# 2505_IDS_DL_BAT.net
KiCad netlist of a schematic drawn in Altium Designer
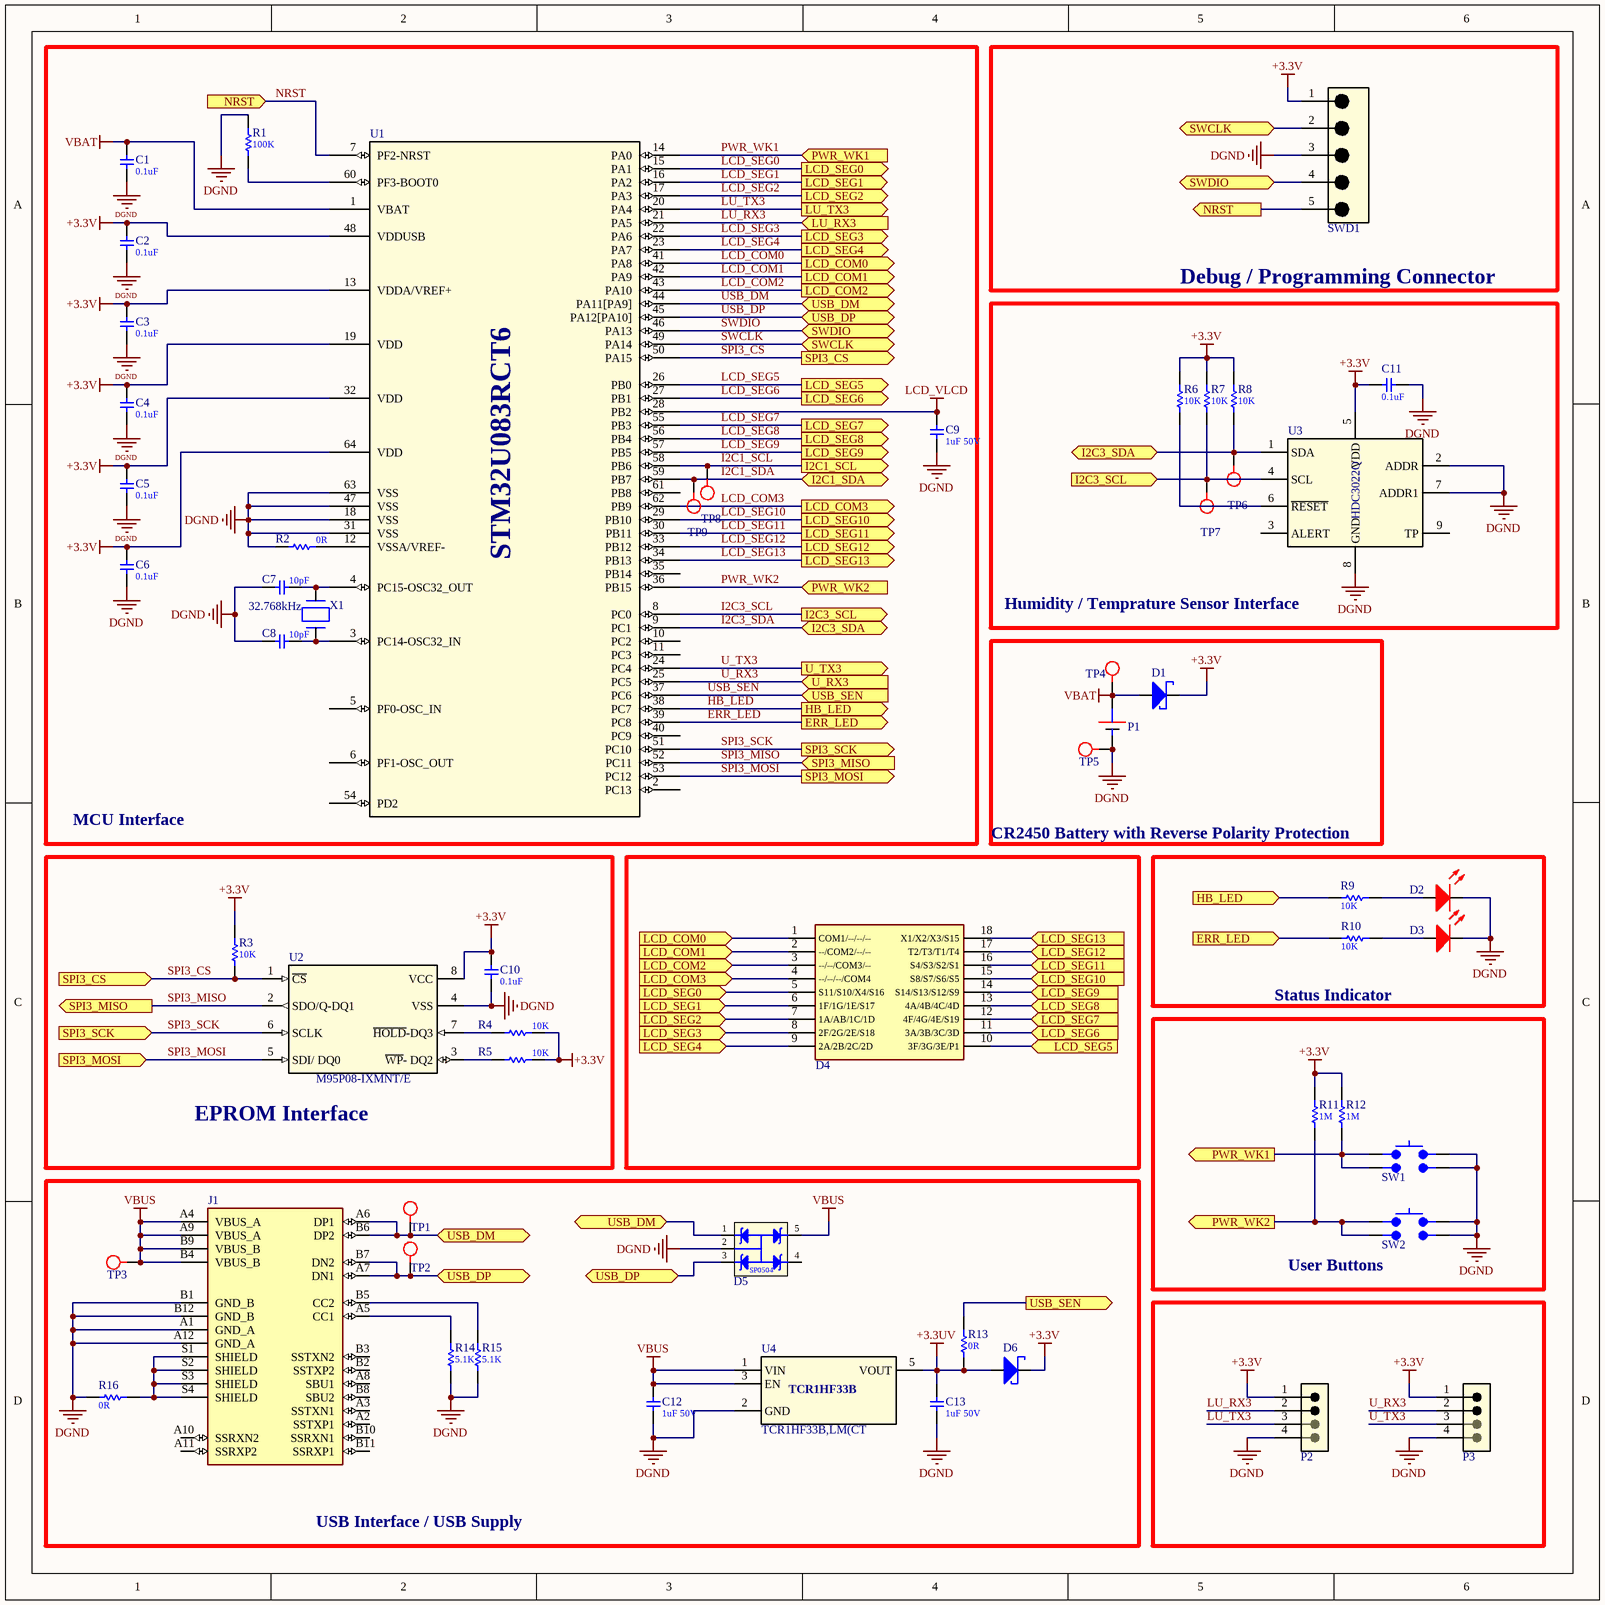
[diagram p0: 2505_IDS_DL_BAT.SchDoc]

(export (version "E")
  (design (tool "Eeschema 10.0.6"))
  (components
    (comp (ref "C1")
      (value "0.1uF")
      (footprint "C_0603 (1608 Metric)")
      (fields
        (field (name "MANUFACTURER PART NO") "CL10B104KB8NNWC")
        (field (name "Comment") "CAP CER 0.1UF 50V X7R 0603")
      )
      (libsource (lib "Capacitor") (part "CAP CER 0.1UF 50V X7R 0603"))
    )
    (comp (ref "C2")
      (value "0.1uF")
      (footprint "C_0603 (1608 Metric)")
      (fields
        (field (name "MANUFACTURER PART NO") "CL10B104KB8NNWC")
        (field (name "Comment") "CAP CER 0.1UF 50V X7R 0603")
      )
      (libsource (lib "Capacitor") (part "CAP CER 0.1UF 50V X7R 0603"))
    )
    (comp (ref "C3")
      (value "0.1uF")
      (footprint "C_0603 (1608 Metric)")
      (fields
        (field (name "MANUFACTURER PART NO") "CL10B104KB8NNWC")
        (field (name "Comment") "CAP CER 0.1UF 50V X7R 0603")
      )
      (libsource (lib "Capacitor") (part "CAP CER 0.1UF 50V X7R 0603"))
    )
    (comp (ref "C4")
      (value "0.1uF")
      (footprint "C_0603 (1608 Metric)")
      (fields
        (field (name "MANUFACTURER PART NO") "CL10B104KB8NNWC")
        (field (name "Comment") "CAP CER 0.1UF 50V X7R 0603")
      )
      (libsource (lib "Capacitor") (part "CAP CER 0.1UF 50V X7R 0603"))
    )
    (comp (ref "C5")
      (value "0.1uF")
      (footprint "C_0603 (1608 Metric)")
      (fields
        (field (name "MANUFACTURER PART NO") "CL10B104KB8NNWC")
        (field (name "Comment") "CAP CER 0.1UF 50V X7R 0603")
      )
      (libsource (lib "Capacitor") (part "CAP CER 0.1UF 50V X7R 0603"))
    )
    (comp (ref "C6")
      (value "0.1uF")
      (footprint "C_0603 (1608 Metric)")
      (fields
        (field (name "MANUFACTURER PART NO") "CL10B104KB8NNWC")
        (field (name "Comment") "CAP CER 0.1UF 50V X7R 0603")
      )
      (libsource (lib "Capacitor") (part "CAP CER 0.1UF 50V X7R 0603"))
    )
    (comp (ref "C7")
      (value "10pF")
      (footprint "C_0603 (1608 Metric)")
      (fields
        (field (name "MANUFACTURER PART NO") "0603N100J500CT")
        (field (name "Comment") "CAP CER 10PF 50V C0G/NP0 0603")
      )
      (libsource (lib "Capacitor") (part "CAP CER 10PF 50V C0G/NP0 0603"))
    )
    (comp (ref "C8")
      (value "10pF")
      (footprint "C_0603 (1608 Metric)")
      (fields
        (field (name "MANUFACTURER PART NO") "0603N100J500CT")
        (field (name "Comment") "CAP CER 10PF 50V C0G/NP0 0603")
      )
      (libsource (lib "Capacitor") (part "CAP CER 10PF 50V C0G/NP0 0603"))
    )
    (comp (ref "C9")
      (value "1uF 50V")
      (footprint "C_0805 (2012 Metric)")
      (fields
        (field (name "MANUFACTURER PART NO") "CL21B105KBFNNNE")
        (field (name "Comment") "CAP CER 1UF 50V X7R 0805")
      )
      (libsource (lib "Capacitor") (part "CAP CER 1UF 50V X7R 0805"))
    )
    (comp (ref "C10")
      (value "0.1uF")
      (footprint "C_0603 (1608 Metric)")
      (fields
        (field (name "MANUFACTURER PART NO") "CL10B104KB8NNWC")
        (field (name "Comment") "CAP CER 0.1UF 50V X7R 0603")
      )
      (libsource (lib "Capacitor") (part "CAP CER 0.1UF 50V X7R 0603"))
    )
    (comp (ref "C11")
      (value "0.1uF")
      (footprint "C_0603 (1608 Metric)")
      (fields
        (field (name "MANUFACTURER PART NO") "CL10B104KB8NNWC")
        (field (name "Comment") "CAP CER 0.1UF 50V X7R 0603")
      )
      (libsource (lib "Capacitor") (part "CAP CER 0.1UF 50V X7R 0603"))
    )
    (comp (ref "C12")
      (value "1uF 50V")
      (footprint "C_0805 (2012 Metric)")
      (fields
        (field (name "MANUFACTURER PART NO") "CL21B105KBFNNNE")
        (field (name "Comment") "CAP CER 1UF 50V X7R 0805")
      )
      (libsource (lib "Capacitor") (part "CAP CER 1UF 50V X7R 0805"))
    )
    (comp (ref "C13")
      (value "1uF 50V")
      (footprint "C_0805 (2012 Metric)")
      (fields
        (field (name "MANUFACTURER PART NO") "CL21B105KBFNNNE")
        (field (name "Comment") "CAP CER 1UF 50V X7R 0805")
      )
      (libsource (lib "Capacitor") (part "CAP CER 1UF 50V X7R 0805"))
    )
    (comp (ref "D1")
      (value "DIODE SCHOTTKY 20V 1A SOD323")
      (footprint "SOD-323")
      (fields (field (name "MANUFACTURER PART NO") "PMEG2010BEA"))
      (libsource (lib "Diode") (part "DIODE SCHOTTKY 20V 1A SOD323"))
    )
    (comp (ref "D2")
      (value "LED RED CLEAR SMD")
      (footprint "L_SMD0805")
      (libsource (lib "Diode") (part "LED RED CLEAR SMD"))
    )
    (comp (ref "D3")
      (value "LED RED CLEAR SMD")
      (footprint "L_SMD0805")
      (libsource (lib "Diode") (part "LED RED CLEAR SMD"))
    )
    (comp (ref "D4")
      (value "LCD_DL_BAT")
      (footprint "LCD_DL_BAT")
      (libsource (lib "LCD") (part "LCD_DL_BAT"))
    )
    (comp (ref "D5")
      (value "TVS DIODE 5.5VWM 8.5VC SOT23-5")
      (footprint "SOT-23-5")
      (fields (field (name "MANUFACTURER PART NO") "SP0504BAHTG"))
      (libsource (lib "Diode") (part "TVS DIODE 5.5VWM 8.5VC SOT23-5"))
    )
    (comp (ref "D6")
      (value "DIODE SCHOTTKY 20V 1A SOD323")
      (footprint "SOD-323")
      (fields (field (name "MANUFACTURER PART NO") "PMEG2010BEA"))
      (libsource (lib "Diode") (part "DIODE SCHOTTKY 20V 1A SOD323"))
    )
    (comp (ref "J1")
      (value "USB-C REC 3\" VERT 24P SMT & TH S")
      (footprint "USB4225-03-1000-C")
      (fields (field (name "MANUFACTURER PART NO") "USB4225-03-1000-C"))
      (libsource (lib "Connector") (part "USB-C REC 3{dblquote} VERT 24P SMT & TH S"))
    )
    (comp (ref "P1")
      (value "BAT CLIP CR2477")
      (footprint "BAT_CLIP_CR2477")
      (fields (field (name "MANUFACTURER PART NO") "CST-2450M  /CST-2450P"))
      (libsource (lib "Connector") (part "BAT CLIP CR2477"))
    )
    (comp (ref "P2")
      (value "WR-PHD 1x4 2.00 MM PIN HEADER")
      (footprint "62000411121")
      (fields (field (name "MANUFACTURER PART NO") "62000411121"))
      (libsource (lib "Connector") (part "WR-PHD 1x4 2.00 MM PIN HEADER"))
    )
    (comp (ref "P3")
      (value "WR-PHD 1x4 2.00 MM PIN HEADER")
      (footprint "62000411121")
      (fields (field (name "MANUFACTURER PART NO") "62000411121"))
      (libsource (lib "Connector") (part "WR-PHD 1x4 2.00 MM PIN HEADER"))
    )
    (comp (ref "R1")
      (value "100K")
      (footprint "0603 (1608 Metric)")
      (fields
        (field (name "MANUFACTURER PART NO") "RMCF0603FT100K")
        (field (name "Comment") "RES 100K OHM 1% 1/10W 0603")
      )
      (libsource (lib "Resistor") (part "RES 100K OHM 1% 1/10W 0603"))
    )
    (comp (ref "R2")
      (value "0R")
      (footprint "0402 (1005 Metric)")
      (fields
        (field (name "MANUFACTURER PART NO") "RC0402JR-070RP")
        (field (name "Comment") "RES 0 OHM JUMPER - 0402")
      )
      (libsource (lib "Resistor") (part "RES 0 OHM JUMPER - 0402"))
    )
    (comp (ref "R3")
      (value "10K")
      (footprint "0603 (1608 Metric)")
      (fields
        (field (name "MANUFACTURER PART NO") "RMCF0603FT10K0")
        (field (name "Comment") "RES 10K OHM 1% 1/10W 0603")
      )
      (libsource (lib "Resistor") (part "RES 10K OHM 1% 1/10W 0603"))
    )
    (comp (ref "R4")
      (value "10K")
      (footprint "0603 (1608 Metric)")
      (fields
        (field (name "MANUFACTURER PART NO") "RMCF0603FT10K0")
        (field (name "Comment") "RES 10K OHM 1% 1/10W 0603")
      )
      (libsource (lib "Resistor") (part "RES 10K OHM 1% 1/10W 0603"))
    )
    (comp (ref "R5")
      (value "10K")
      (footprint "0603 (1608 Metric)")
      (fields
        (field (name "MANUFACTURER PART NO") "RMCF0603FT10K0")
        (field (name "Comment") "RES 10K OHM 1% 1/10W 0603")
      )
      (libsource (lib "Resistor") (part "RES 10K OHM 1% 1/10W 0603"))
    )
    (comp (ref "R6")
      (value "10K")
      (footprint "0603 (1608 Metric)")
      (fields
        (field (name "MANUFACTURER PART NO") "RMCF0603FT10K0")
        (field (name "Comment") "RES 10K OHM 1% 1/10W 0603")
      )
      (libsource (lib "Resistor") (part "RES 10K OHM 1% 1/10W 0603"))
    )
    (comp (ref "R7")
      (value "10K")
      (footprint "0603 (1608 Metric)")
      (fields
        (field (name "MANUFACTURER PART NO") "RMCF0603FT10K0")
        (field (name "Comment") "RES 10K OHM 1% 1/10W 0603")
      )
      (libsource (lib "Resistor") (part "RES 10K OHM 1% 1/10W 0603"))
    )
    (comp (ref "R8")
      (value "10K")
      (footprint "0603 (1608 Metric)")
      (fields
        (field (name "MANUFACTURER PART NO") "RMCF0603FT10K0")
        (field (name "Comment") "RES 10K OHM 1% 1/10W 0603")
      )
      (libsource (lib "Resistor") (part "RES 10K OHM 1% 1/10W 0603"))
    )
    (comp (ref "R9")
      (value "10K")
      (footprint "0603 (1608 Metric)")
      (fields
        (field (name "MANUFACTURER PART NO") "RMCF0603FT10K0")
        (field (name "Comment") "RES 10K OHM 1% 1/10W 0603")
      )
      (libsource (lib "Resistor") (part "RES 10K OHM 1% 1/10W 0603"))
    )
    (comp (ref "R10")
      (value "10K")
      (footprint "0603 (1608 Metric)")
      (fields
        (field (name "MANUFACTURER PART NO") "RMCF0603FT10K0")
        (field (name "Comment") "RES 10K OHM 1% 1/10W 0603")
      )
      (libsource (lib "Resistor") (part "RES 10K OHM 1% 1/10W 0603"))
    )
    (comp (ref "R11")
      (value "1M")
      (footprint "0603 (1608 Metric)")
      (fields
        (field (name "MANUFACTURER PART NO") "WR06X1004FTL")
        (field (name "Comment") "RES 1M OHM 1% 1/10W 0603")
      )
      (libsource (lib "Resistor") (part "RES 1M OHM 1% 1/10W 0603"))
    )
    (comp (ref "R12")
      (value "1M")
      (footprint "0603 (1608 Metric)")
      (fields
        (field (name "MANUFACTURER PART NO") "WR06X1004FTL")
        (field (name "Comment") "RES 1M OHM 1% 1/10W 0603")
      )
      (libsource (lib "Resistor") (part "RES 1M OHM 1% 1/10W 0603"))
    )
    (comp (ref "R13")
      (value "0R")
      (footprint "0402 (1005 Metric)")
      (fields
        (field (name "MANUFACTURER PART NO") "RC0402JR-070RP")
        (field (name "Comment") "RES 0 OHM JUMPER - 0402")
      )
      (libsource (lib "Resistor") (part "RES 0 OHM JUMPER - 0402"))
    )
    (comp (ref "R14")
      (value "5.1K")
      (footprint "0603 (1608 Metric)")
      (fields
        (field (name "MANUFACTURER PART NO") "RMCF0603FT5K10")
        (field (name "Comment") "RES 5.1K OHM 1% 1/10W 0603")
      )
      (libsource (lib "Resistor") (part "RES 5.1K OHM 1% 1/10W 0603"))
    )
    (comp (ref "R15")
      (value "5.1K")
      (footprint "0603 (1608 Metric)")
      (fields
        (field (name "MANUFACTURER PART NO") "RMCF0603FT5K10")
        (field (name "Comment") "RES 5.1K OHM 1% 1/10W 0603")
      )
      (libsource (lib "Resistor") (part "RES 5.1K OHM 1% 1/10W 0603"))
    )
    (comp (ref "R16")
      (value "0R")
      (footprint "0402 (1005 Metric)")
      (fields
        (field (name "MANUFACTURER PART NO") "RC0402JR-070RP")
        (field (name "Comment") "RES 0 OHM JUMPER - 0402")
      )
      (libsource (lib "Resistor") (part "RES 0 OHM JUMPER - 0402"))
    )
    (comp (ref "SW1")
      (value "SWITCH TACTILE SPST-NO 0.05A 12V")
      (footprint "TL3305AF260QG")
      (fields (field (name "MANUFACTURER PART NO") "TL3305AF260QG"))
      (libsource (lib "Switch") (part "SWITCH TACTILE SPST-NO 0.05A 12V"))
    )
    (comp (ref "SW2")
      (value "SWITCH TACTILE SPST-NO 0.05A 12V")
      (footprint "TL3305AF260QG")
      (fields (field (name "MANUFACTURER PART NO") "TL3305AF260QG"))
      (libsource (lib "Switch") (part "SWITCH TACTILE SPST-NO 0.05A 12V"))
    )
    (comp (ref "SWD1")
      (value "CONN HEADER VERT 5POS 2.54MM")
      (footprint "Burg Stick 1x5 2.54mm")
      (fields (field (name "MANUFACTURER PART NO") "61300511121"))
      (libsource (lib "Connector") (part "CONN HEADER VERT 5POS 2.54MM"))
    )
    (comp (ref "TP1")
      (value "Test Point")
      (footprint "Testpoint 1.02mm PTH")
      (libsource (lib "Connector") (part "Test Point"))
    )
    (comp (ref "TP2")
      (value "Test Point")
      (footprint "Testpoint 1.02mm PTH")
      (libsource (lib "Connector") (part "Test Point"))
    )
    (comp (ref "TP3")
      (value "Test Point")
      (footprint "Testpoint 1.02mm PTH")
      (libsource (lib "Connector") (part "Test Point"))
    )
    (comp (ref "TP4")
      (value "Test Point")
      (footprint "Testpoint 1.02mm PTH")
      (libsource (lib "Connector") (part "Test Point"))
    )
    (comp (ref "TP5")
      (value "Test Point")
      (footprint "Testpoint 1.02mm PTH")
      (libsource (lib "Connector") (part "Test Point"))
    )
    (comp (ref "TP6")
      (value "Test Point")
      (footprint "Testpoint 1.02mm PTH")
      (libsource (lib "Connector") (part "Test Point"))
    )
    (comp (ref "TP7")
      (value "Test Point")
      (footprint "Testpoint 1.02mm PTH")
      (libsource (lib "Connector") (part "Test Point"))
    )
    (comp (ref "TP8")
      (value "Test Point SMD")
      (footprint "Test_PointSMD")
      (libsource (lib "Connector") (part "Test Point SMD"))
    )
    (comp (ref "TP9")
      (value "Test Point SMD")
      (footprint "Test_PointSMD")
      (libsource (lib "Connector") (part "Test Point SMD"))
    )
    (comp (ref "U1")
      (value "STM32U083RCT6")
      (footprint "64-LQFP")
      (fields (field (name "Comment") "IC MCU STM32U083RCT6 64LQFP"))
      (libsource (lib "IC") (part "STM32U083RCT6"))
    )
    (comp (ref "U2")
      (value "IC EEPROM 8MBIT SPI/QUAD 8SOIC")
      (footprint "8-SOIC (0.154\", 3.90mm Width)")
      (fields (field (name "MANUFACTURER PART NO") "M95P08-IXMNT/E"))
      (libsource (lib "IC") (part "M95P08-IXMNT/E"))
    )
    (comp (ref "U3")
      (value "RH DIGITAL HUMIDITY SENSOR")
      (footprint "8-LFDFN Exposed Pad")
      (fields (field (name "MANUFACTURER PART NO") "HDC3022QDEJRQ1"))
      (libsource (lib "IC") (part "HDC3022QDEJRQ1"))
    )
    (comp (ref "U4")
      (value "TCR1HF33B,LM(CT")
      (footprint "SC-74A, SOT-753")
      (fields (field (name "Comment") "IC REG LINEAR 3.3V 150MA SMV"))
      (libsource (lib "IC") (part "TCR1HF33B,LM(CT"))
    )
    (comp (ref "X1")
      (value "32.768kHz")
      (footprint "CRY_NX2012SA_2P")
      (description "CRYSTAL 32.7680KHZ 7PF SMD")
      (fields (field (name "MANUFACTURER PART NO") "NX2012SA-32.768KHZ-EXS00A-MU00389"))
      (libsource (lib "MB2032") (part "CRYSTAL 32.7680KHZ 7PF SMD"))
    )
  )
  (nets
    (net (code "1") (name "+3.3UV") (class "Default")
      (node (ref "C13") (pin "2") (pinfunction "2_2") (pintype "passive"))
      (node (ref "D6") (pin "2") (pinfunction "A_2") (pintype "passive"))
      (node (ref "R13") (pin "1") (pinfunction "1_1") (pintype "passive"))
      (node (ref "U4") (pin "5") (pinfunction "VOUT_5") (pintype "power_in"))
    )
    (net (code "2") (name "+3.3V") (class "Default")
      (node (ref "C10") (pin "1") (pinfunction "1_1") (pintype "passive"))
      (node (ref "C11") (pin "1") (pinfunction "1_1") (pintype "passive"))
      (node (ref "C2") (pin "2") (pinfunction "2_2") (pintype "passive"))
      (node (ref "C3") (pin "2") (pinfunction "2_2") (pintype "passive"))
      (node (ref "C4") (pin "2") (pinfunction "2_2") (pintype "passive"))
      (node (ref "C5") (pin "2") (pinfunction "2_2") (pintype "passive"))
      (node (ref "C6") (pin "2") (pinfunction "2_2") (pintype "passive"))
      (node (ref "D1") (pin "1") (pinfunction "K_1") (pintype "passive"))
      (node (ref "D6") (pin "1") (pinfunction "K_1") (pintype "passive"))
      (node (ref "P2") (pin "1") (pinfunction "1_1") (pintype "passive"))
      (node (ref "P3") (pin "1") (pinfunction "1_1") (pintype "passive"))
      (node (ref "R11") (pin "2") (pinfunction "2_2") (pintype "passive"))
      (node (ref "R12") (pin "2") (pinfunction "2_2") (pintype "passive"))
      (node (ref "R3") (pin "2") (pinfunction "2_2") (pintype "passive"))
      (node (ref "R4") (pin "2") (pinfunction "2_2") (pintype "passive"))
      (node (ref "R5") (pin "2") (pinfunction "2_2") (pintype "passive"))
      (node (ref "R6") (pin "2") (pinfunction "2_2") (pintype "passive"))
      (node (ref "R7") (pin "2") (pinfunction "2_2") (pintype "passive"))
      (node (ref "R8") (pin "2") (pinfunction "2_2") (pintype "passive"))
      (node (ref "SWD1") (pin "1") (pinfunction "1_1") (pintype "passive"))
      (node (ref "U1") (pin "13") (pinfunction "VDDA/VREF+_13") (pintype "power_in"))
      (node (ref "U1") (pin "19") (pinfunction "VDD_19") (pintype "power_in"))
      (node (ref "U1") (pin "32") (pinfunction "VDD_32") (pintype "power_in"))
      (node (ref "U1") (pin "48") (pinfunction "VDDUSB_48") (pintype "power_in"))
      (node (ref "U1") (pin "64") (pinfunction "VDD_64") (pintype "power_in"))
      (node (ref "U2") (pin "8") (pinfunction "VCC_8") (pintype "power_in"))
      (node (ref "U3") (pin "5") (pinfunction "VDD_5") (pintype "open_collector"))
    )
    (net (code "3") (name "/ERR_LED") (class "Default")
      (node (ref "R10") (pin "1") (pinfunction "1_1") (pintype "passive"))
      (node (ref "U1") (pin "39") (pinfunction "PC8_39") (pintype "bidirectional"))
    )
    (net (code "4") (name "/HB_LED") (class "Default")
      (node (ref "R9") (pin "1") (pinfunction "1_1") (pintype "passive"))
      (node (ref "U1") (pin "38") (pinfunction "PC7_38") (pintype "bidirectional"))
    )
    (net (code "5") (name "/I2C1_SCL") (class "Default")
      (node (ref "TP8") (pin "1") (pinfunction "1_1") (pintype "passive"))
      (node (ref "U1") (pin "58") (pinfunction "PB6_58") (pintype "bidirectional"))
    )
    (net (code "6") (name "/I2C1_SDA") (class "Default")
      (node (ref "TP9") (pin "1") (pinfunction "1_1") (pintype "passive"))
      (node (ref "U1") (pin "59") (pinfunction "PB7_59") (pintype "bidirectional"))
    )
    (net (code "7") (name "/I2C3_SCL") (class "Default")
      (node (ref "R7") (pin "1") (pinfunction "1_1") (pintype "passive"))
      (node (ref "TP7") (pin "1") (pinfunction "1_1") (pintype "passive"))
      (node (ref "U1") (pin "8") (pinfunction "PC0_8") (pintype "bidirectional"))
      (node (ref "U3") (pin "4") (pinfunction "SCL_4") (pintype "open_collector"))
    )
    (net (code "8") (name "/I2C3_SDA") (class "Default")
      (node (ref "R8") (pin "1") (pinfunction "1_1") (pintype "passive"))
      (node (ref "TP6") (pin "1") (pinfunction "1_1") (pintype "passive"))
      (node (ref "U1") (pin "9") (pinfunction "PC1_9") (pintype "bidirectional"))
      (node (ref "U3") (pin "1") (pinfunction "SDA_1") (pintype "power_in"))
    )
    (net (code "9") (name "/LCD_COM0") (class "Default")
      (node (ref "D4") (pin "1") (pinfunction "COM1/--/--/--_1") (pintype "passive"))
      (node (ref "U1") (pin "41") (pinfunction "PA8_41") (pintype "bidirectional"))
    )
    (net (code "10") (name "/LCD_COM1") (class "Default")
      (node (ref "D4") (pin "2") (pinfunction "--/COM2/--/--_2") (pintype "passive"))
      (node (ref "U1") (pin "42") (pinfunction "PA9_42") (pintype "bidirectional"))
    )
    (net (code "11") (name "/LCD_COM2") (class "Default")
      (node (ref "D4") (pin "3") (pinfunction "--/--/COM3/--_3") (pintype "passive"))
      (node (ref "U1") (pin "43") (pinfunction "PA10_43") (pintype "bidirectional"))
    )
    (net (code "12") (name "/LCD_COM3") (class "Default")
      (node (ref "D4") (pin "4") (pinfunction "--/--/--/COM4_4") (pintype "passive"))
      (node (ref "U1") (pin "62") (pinfunction "PB9_62") (pintype "bidirectional"))
    )
    (net (code "13") (name "/LCD_SEG0") (class "Default")
      (node (ref "D4") (pin "5") (pinfunction "S11/S10/X4/S16_5") (pintype "passive"))
      (node (ref "U1") (pin "15") (pinfunction "PA1_15") (pintype "bidirectional"))
    )
    (net (code "14") (name "/LCD_SEG1") (class "Default")
      (node (ref "D4") (pin "6") (pinfunction "1F/1G/1E/S17_6") (pintype "passive"))
      (node (ref "U1") (pin "16") (pinfunction "PA2_16") (pintype "bidirectional"))
    )
    (net (code "15") (name "/LCD_SEG2") (class "Default")
      (node (ref "D4") (pin "7") (pinfunction "1A/AB/1C/1D_7") (pintype "passive"))
      (node (ref "U1") (pin "17") (pinfunction "PA3_17") (pintype "bidirectional"))
    )
    (net (code "16") (name "/LCD_SEG3") (class "Default")
      (node (ref "D4") (pin "8") (pinfunction "2F/2G/2E/S18_8") (pintype "passive"))
      (node (ref "U1") (pin "22") (pinfunction "PA6_22") (pintype "bidirectional"))
    )
    (net (code "17") (name "/LCD_SEG4") (class "Default")
      (node (ref "D4") (pin "9") (pinfunction "2A/2B/2C/2D_9") (pintype "passive"))
      (node (ref "U1") (pin "23") (pinfunction "PA7_23") (pintype "bidirectional"))
    )
    (net (code "18") (name "/LCD_SEG5") (class "Default")
      (node (ref "D4") (pin "10") (pinfunction "3F/3G/3E/P1_10") (pintype "passive"))
      (node (ref "U1") (pin "26") (pinfunction "PB0_26") (pintype "bidirectional"))
    )
    (net (code "19") (name "/LCD_SEG6") (class "Default")
      (node (ref "D4") (pin "11") (pinfunction "3A/3B/3C/3D_11") (pintype "passive"))
      (node (ref "U1") (pin "27") (pinfunction "PB1_27") (pintype "bidirectional"))
    )
    (net (code "20") (name "/LCD_SEG7") (class "Default")
      (node (ref "D4") (pin "12") (pinfunction "4F/4G/4E/S19_12") (pintype "passive"))
      (node (ref "U1") (pin "55") (pinfunction "PB3_55") (pintype "bidirectional"))
    )
    (net (code "21") (name "/LCD_SEG8") (class "Default")
      (node (ref "D4") (pin "13") (pinfunction "4A/4B/4C/4D_13") (pintype "passive"))
      (node (ref "U1") (pin "56") (pinfunction "PB4_56") (pintype "bidirectional"))
    )
    (net (code "22") (name "/LCD_SEG9") (class "Default")
      (node (ref "D4") (pin "14") (pinfunction "S14/S13/S12/S9_14") (pintype "passive"))
      (node (ref "U1") (pin "57") (pinfunction "PB5_57") (pintype "bidirectional"))
    )
    (net (code "23") (name "/LCD_SEG10") (class "Default")
      (node (ref "D4") (pin "15") (pinfunction "S8/S7/S6/S5_15") (pintype "passive"))
      (node (ref "U1") (pin "29") (pinfunction "PB10_29") (pintype "bidirectional"))
    )
    (net (code "24") (name "/LCD_SEG11") (class "Default")
      (node (ref "D4") (pin "16") (pinfunction "S4/S3/S2/S1_16") (pintype "passive"))
      (node (ref "U1") (pin "30") (pinfunction "PB11_30") (pintype "bidirectional"))
    )
    (net (code "25") (name "/LCD_SEG12") (class "Default")
      (node (ref "D4") (pin "17") (pinfunction "T2/T3/T1/T4_17") (pintype "passive"))
      (node (ref "U1") (pin "33") (pinfunction "PB12_33") (pintype "bidirectional"))
    )
    (net (code "26") (name "/LCD_SEG13") (class "Default")
      (node (ref "D4") (pin "18") (pinfunction "X1/X2/X3/S15_18") (pintype "passive"))
      (node (ref "U1") (pin "34") (pinfunction "PB13_34") (pintype "bidirectional"))
    )
    (net (code "27") (name "/LU_RX3") (class "Default")
      (node (ref "P2") (pin "2") (pinfunction "2_2") (pintype "passive"))
      (node (ref "U1") (pin "21") (pinfunction "PA5_21") (pintype "bidirectional"))
    )
    (net (code "28") (name "/LU_TX3") (class "Default")
      (node (ref "P2") (pin "3") (pinfunction "3_3") (pintype "passive"))
      (node (ref "U1") (pin "20") (pinfunction "PA4_20") (pintype "bidirectional"))
    )
    (net (code "29") (name "/NRST") (class "Default")
      (node (ref "SWD1") (pin "5") (pinfunction "5_5") (pintype "passive"))
      (node (ref "U1") (pin "7") (pinfunction "PF2-NRST_7") (pintype "bidirectional"))
    )
    (net (code "30") (name "/PWR_WK1") (class "Default")
      (node (ref "R12") (pin "1") (pinfunction "1_1") (pintype "passive"))
      (node (ref "SW1") (pin "1") (pinfunction "1_1") (pintype "passive"))
      (node (ref "SW1") (pin "2") (pinfunction "2_2") (pintype "passive"))
      (node (ref "U1") (pin "14") (pinfunction "PA0_14") (pintype "bidirectional"))
    )
    (net (code "31") (name "/PWR_WK2") (class "Default")
      (node (ref "R11") (pin "1") (pinfunction "1_1") (pintype "passive"))
      (node (ref "SW2") (pin "1") (pinfunction "1_1") (pintype "passive"))
      (node (ref "SW2") (pin "2") (pinfunction "2_2") (pintype "passive"))
      (node (ref "U1") (pin "36") (pinfunction "PB15_36") (pintype "bidirectional"))
    )
    (net (code "32") (name "/SPI3_CS") (class "Default")
      (node (ref "R3") (pin "1") (pinfunction "1_1") (pintype "passive"))
      (node (ref "U1") (pin "50") (pinfunction "PA15_50") (pintype "bidirectional"))
      (node (ref "U2") (pin "1") (pinfunction "~{CS}_1") (pintype "input"))
    )
    (net (code "33") (name "/SPI3_MISO") (class "Default")
      (node (ref "U1") (pin "52") (pinfunction "PC11_52") (pintype "bidirectional"))
      (node (ref "U2") (pin "2") (pinfunction "SDO/Q-DQ1_2") (pintype "output"))
    )
    (net (code "34") (name "/SPI3_MOSI") (class "Default")
      (node (ref "U1") (pin "53") (pinfunction "PC12_53") (pintype "bidirectional"))
      (node (ref "U2") (pin "5") (pinfunction "SDI/_DQ0_5") (pintype "input"))
    )
    (net (code "35") (name "/SPI3_SCK") (class "Default")
      (node (ref "U1") (pin "51") (pinfunction "PC10_51") (pintype "bidirectional"))
      (node (ref "U2") (pin "6") (pinfunction "SCLK_6") (pintype "input"))
    )
    (net (code "36") (name "/SWCLK") (class "Default")
      (node (ref "SWD1") (pin "2") (pinfunction "2_2") (pintype "passive"))
      (node (ref "U1") (pin "49") (pinfunction "PA14_49") (pintype "bidirectional"))
    )
    (net (code "37") (name "/SWDIO") (class "Default")
      (node (ref "SWD1") (pin "4") (pinfunction "4_4") (pintype "passive"))
      (node (ref "U1") (pin "46") (pinfunction "PA13_46") (pintype "bidirectional"))
    )
    (net (code "38") (name "/USB_DM") (class "Default")
      (node (ref "D5") (pin "1") (pinfunction "1_1") (pintype "passive"))
      (node (ref "J1") (pin "A6") (pinfunction "DP1_A6") (pintype "bidirectional"))
      (node (ref "J1") (pin "B6") (pinfunction "DP2_B6") (pintype "bidirectional"))
      (node (ref "TP1") (pin "1") (pinfunction "1_1") (pintype "passive"))
      (node (ref "U1") (pin "44") (pinfunction "PA11[PA9]_44") (pintype "bidirectional"))
    )
    (net (code "39") (name "/USB_DP") (class "Default")
      (node (ref "D5") (pin "3") (pinfunction "3_3") (pintype "passive"))
      (node (ref "J1") (pin "A7") (pinfunction "DN1_A7") (pintype "bidirectional"))
      (node (ref "J1") (pin "B7") (pinfunction "DN2_B7") (pintype "bidirectional"))
      (node (ref "TP2") (pin "1") (pinfunction "1_1") (pintype "passive"))
      (node (ref "U1") (pin "45") (pinfunction "PA12[PA10]_45") (pintype "bidirectional"))
    )
    (net (code "40") (name "/USB_SEN") (class "Default")
      (node (ref "R13") (pin "2") (pinfunction "2_2") (pintype "passive"))
      (node (ref "U1") (pin "37") (pinfunction "PC6_37") (pintype "bidirectional"))
    )
    (net (code "41") (name "/U_RX3") (class "Default")
      (node (ref "P3") (pin "2") (pinfunction "2_2") (pintype "passive"))
      (node (ref "U1") (pin "25") (pinfunction "PC5_25") (pintype "bidirectional"))
    )
    (net (code "42") (name "/U_TX3") (class "Default")
      (node (ref "P3") (pin "3") (pinfunction "3_3") (pintype "passive"))
      (node (ref "U1") (pin "24") (pinfunction "PC4_24") (pintype "bidirectional"))
    )
    (net (code "43") (name "DGND") (class "Default")
      (node (ref "C1") (pin "1") (pinfunction "1_1") (pintype "passive"))
      (node (ref "C10") (pin "2") (pinfunction "2_2") (pintype "passive"))
      (node (ref "C11") (pin "2") (pinfunction "2_2") (pintype "passive"))
      (node (ref "C12") (pin "1") (pinfunction "1_1") (pintype "passive"))
      (node (ref "C13") (pin "1") (pinfunction "1_1") (pintype "passive"))
      (node (ref "C2") (pin "1") (pinfunction "1_1") (pintype "passive"))
      (node (ref "C3") (pin "1") (pinfunction "1_1") (pintype "passive"))
      (node (ref "C4") (pin "1") (pinfunction "1_1") (pintype "passive"))
      (node (ref "C5") (pin "1") (pinfunction "1_1") (pintype "passive"))
      (node (ref "C6") (pin "1") (pinfunction "1_1") (pintype "passive"))
      (node (ref "C7") (pin "1") (pinfunction "1_1") (pintype "passive"))
      (node (ref "C8") (pin "1") (pinfunction "1_1") (pintype "passive"))
      (node (ref "C9") (pin "1") (pinfunction "1_1") (pintype "passive"))
      (node (ref "D2") (pin "2") (pinfunction "K_2") (pintype "passive"))
      (node (ref "D3") (pin "2") (pinfunction "K_2") (pintype "passive"))
      (node (ref "D5") (pin "2") (pinfunction "2_2") (pintype "passive"))
      (node (ref "J1") (pin "A1") (pinfunction "GND_A_A1") (pintype "power_in"))
      (node (ref "J1") (pin "A12") (pinfunction "GND_A_A12") (pintype "power_in"))
      (node (ref "J1") (pin "B1") (pinfunction "GND_B_B1") (pintype "power_in"))
      (node (ref "J1") (pin "B12") (pinfunction "GND_B_B12") (pintype "power_in"))
      (node (ref "P1") (pin "2") (pinfunction "-_2") (pintype "passive"))
      (node (ref "P2") (pin "4") (pinfunction "4_4") (pintype "passive"))
      (node (ref "P3") (pin "4") (pinfunction "4_4") (pintype "passive"))
      (node (ref "R1") (pin "2") (pinfunction "2_2") (pintype "passive"))
      (node (ref "R14") (pin "1") (pinfunction "1_1") (pintype "passive"))
      (node (ref "R15") (pin "1") (pinfunction "1_1") (pintype "passive"))
      (node (ref "R16") (pin "1") (pinfunction "1_1") (pintype "passive"))
      (node (ref "R2") (pin "1") (pinfunction "1_1") (pintype "passive"))
      (node (ref "SW1") (pin "3") (pinfunction "3_3") (pintype "passive"))
      (node (ref "SW1") (pin "4") (pinfunction "4_4") (pintype "passive"))
      (node (ref "SW2") (pin "3") (pinfunction "3_3") (pintype "passive"))
      (node (ref "SW2") (pin "4") (pinfunction "4_4") (pintype "passive"))
      (node (ref "SWD1") (pin "3") (pinfunction "3_3") (pintype "passive"))
      (node (ref "TP5") (pin "1") (pinfunction "1_1") (pintype "passive"))
      (node (ref "U1") (pin "18") (pinfunction "VSS_18") (pintype "power_in"))
      (node (ref "U1") (pin "31") (pinfunction "VSS_31") (pintype "power_in"))
      (node (ref "U1") (pin "47") (pinfunction "VSS_47") (pintype "power_in"))
      (node (ref "U1") (pin "63") (pinfunction "VSS_63") (pintype "power_in"))
      (node (ref "U2") (pin "4") (pinfunction "VSS_4") (pintype "power_in"))
      (node (ref "U3") (pin "2") (pinfunction "ADDR_2") (pintype "power_in"))
      (node (ref "U3") (pin "7") (pinfunction "ADDR1_7") (pintype "open_collector"))
      (node (ref "U3") (pin "8") (pinfunction "GND_8") (pintype "power_in"))
      (node (ref "U4") (pin "2") (pinfunction "GND_2") (pintype "power_in"))
    )
    (net (code "44") (name "LCD_VLCD") (class "Default")
      (node (ref "C9") (pin "2") (pinfunction "2_2") (pintype "passive"))
      (node (ref "U1") (pin "28") (pinfunction "PB2_28") (pintype "bidirectional"))
    )
    (net (code "45") (name "Net-(D2-A)") (class "Default")
      (node (ref "D2") (pin "1") (pinfunction "A_1") (pintype "passive"))
      (node (ref "R9") (pin "2") (pinfunction "2_2") (pintype "passive"))
    )
    (net (code "46") (name "Net-(D3-A)") (class "Default")
      (node (ref "D3") (pin "1") (pinfunction "A_1") (pintype "passive"))
      (node (ref "R10") (pin "2") (pinfunction "2_2") (pintype "passive"))
    )
    (net (code "47") (name "Net-(J1-CC1)") (class "Default")
      (node (ref "J1") (pin "A5") (pinfunction "CC1_A5") (pintype "bidirectional"))
      (node (ref "R14") (pin "2") (pinfunction "2_2") (pintype "passive"))
    )
    (net (code "48") (name "Net-(J1-CC2)") (class "Default")
      (node (ref "J1") (pin "B5") (pinfunction "CC2_B5") (pintype "bidirectional"))
      (node (ref "R15") (pin "2") (pinfunction "2_2") (pintype "passive"))
    )
    (net (code "49") (name "Net-(J1-SHIELD-PadS1)") (class "Default")
      (node (ref "J1") (pin "S1") (pinfunction "SHIELD_S1") (pintype "passive"))
      (node (ref "J1") (pin "S2") (pinfunction "SHIELD_S2") (pintype "passive"))
      (node (ref "J1") (pin "S3") (pinfunction "SHIELD_S3") (pintype "passive"))
      (node (ref "J1") (pin "S4") (pinfunction "SHIELD_S4") (pintype "passive"))
      (node (ref "R16") (pin "2") (pinfunction "2_2") (pintype "passive"))
    )
    (net (code "50") (name "Net-(U1-PC14-OSC32_IN)") (class "Default")
      (node (ref "C8") (pin "2") (pinfunction "2_2") (pintype "passive"))
      (node (ref "U1") (pin "3") (pinfunction "PC14-OSC32_IN_3") (pintype "bidirectional"))
      (node (ref "X1") (pin "1") (pinfunction "X1_1") (pintype "passive"))
    )
    (net (code "51") (name "Net-(U1-PC15-OSC32_OUT)") (class "Default")
      (node (ref "C7") (pin "2") (pinfunction "2_2") (pintype "passive"))
      (node (ref "U1") (pin "4") (pinfunction "PC15-OSC32_OUT_4") (pintype "bidirectional"))
      (node (ref "X1") (pin "2") (pinfunction "X2_2") (pintype "passive"))
    )
    (net (code "52") (name "Net-(U1-PF3-BOOT0)") (class "Default")
      (node (ref "R1") (pin "1") (pinfunction "1_1") (pintype "passive"))
      (node (ref "U1") (pin "60") (pinfunction "PF3-BOOT0_60") (pintype "bidirectional"))
    )
    (net (code "53") (name "Net-(U1-VSSA{slash}VREF-)") (class "Default")
      (node (ref "R2") (pin "2") (pinfunction "2_2") (pintype "passive"))
      (node (ref "U1") (pin "12") (pinfunction "VSSA/VREF-_12") (pintype "power_in"))
    )
    (net (code "54") (name "Net-(U2-~{HOLD}-DQ3)") (class "Default")
      (node (ref "R4") (pin "1") (pinfunction "1_1") (pintype "passive"))
      (node (ref "U2") (pin "7") (pinfunction "~{HOLD}-DQ3_7") (pintype "input"))
    )
    (net (code "55") (name "Net-(U2-~{WP}-_DQ2)") (class "Default")
      (node (ref "R5") (pin "1") (pinfunction "1_1") (pintype "passive"))
      (node (ref "U2") (pin "3") (pinfunction "~{WP}-_DQ2_3") (pintype "bidirectional"))
    )
    (net (code "56") (name "Net-(U3-~{RESET})") (class "Default")
      (node (ref "R6") (pin "1") (pinfunction "1_1") (pintype "passive"))
      (node (ref "U3") (pin "6") (pinfunction "~{RESET}_6") (pintype "open_collector"))
    )
    (net (code "57") (name "VBAT") (class "Default")
      (node (ref "C1") (pin "2") (pinfunction "2_2") (pintype "passive"))
      (node (ref "D1") (pin "2") (pinfunction "A_2") (pintype "passive"))
      (node (ref "P1") (pin "1") (pinfunction "+_1") (pintype "passive"))
      (node (ref "TP4") (pin "1") (pinfunction "1_1") (pintype "passive"))
      (node (ref "U1") (pin "1") (pinfunction "VBAT_1") (pintype "power_in"))
    )
    (net (code "58") (name "VBUS") (class "Default")
      (node (ref "C12") (pin "2") (pinfunction "2_2") (pintype "passive"))
      (node (ref "D5") (pin "5") (pinfunction "5_5") (pintype "passive"))
      (node (ref "J1") (pin "A4") (pinfunction "VBUS_A_A4") (pintype "power_in"))
      (node (ref "J1") (pin "A9") (pinfunction "VBUS_A_A9") (pintype "power_in"))
      (node (ref "J1") (pin "B4") (pinfunction "VBUS_B_B4") (pintype "power_in"))
      (node (ref "J1") (pin "B9") (pinfunction "VBUS_B_B9") (pintype "power_in"))
      (node (ref "TP3") (pin "1") (pinfunction "1_1") (pintype "passive"))
      (node (ref "U4") (pin "1") (pinfunction "VIN_1") (pintype "power_in"))
      (node (ref "U4") (pin "3") (pinfunction "EN_3") (pintype "power_in"))
    )
    (net (code "59") (name "unconnected-(D5-Pad4)") (class "Default")
      (node (ref "D5") (pin "4") (pinfunction "4_4") (pintype "passive"))
    )
    (net (code "60") (name "unconnected-(J1-SBU1-PadA8)") (class "Default")
      (node (ref "J1") (pin "A8") (pinfunction "SBU1_A8") (pintype "bidirectional"))
    )
    (net (code "61") (name "unconnected-(J1-SBU2-PadB8)") (class "Default")
      (node (ref "J1") (pin "B8") (pinfunction "SBU2_B8") (pintype "bidirectional"))
    )
    (net (code "62") (name "unconnected-(J1-SSRXN1-PadB10)") (class "Default")
      (node (ref "J1") (pin "B10") (pinfunction "SSRXN1_B10") (pintype "bidirectional"))
    )
    (net (code "63") (name "unconnected-(J1-SSRXN2-PadA10)") (class "Default")
      (node (ref "J1") (pin "A10") (pinfunction "SSRXN2_A10") (pintype "bidirectional"))
    )
    (net (code "64") (name "unconnected-(J1-SSRXP1-PadB11)") (class "Default")
      (node (ref "J1") (pin "B11") (pinfunction "SSRXP1_B11") (pintype "bidirectional"))
    )
    (net (code "65") (name "unconnected-(J1-SSRXP2-PadA11)") (class "Default")
      (node (ref "J1") (pin "A11") (pinfunction "SSRXP2_A11") (pintype "bidirectional"))
    )
    (net (code "66") (name "unconnected-(J1-SSTXN1-PadA3)") (class "Default")
      (node (ref "J1") (pin "A3") (pinfunction "SSTXN1_A3") (pintype "bidirectional"))
    )
    (net (code "67") (name "unconnected-(J1-SSTXN2-PadB3)") (class "Default")
      (node (ref "J1") (pin "B3") (pinfunction "SSTXN2_B3") (pintype "bidirectional"))
    )
    (net (code "68") (name "unconnected-(J1-SSTXP1-PadA2)") (class "Default")
      (node (ref "J1") (pin "A2") (pinfunction "SSTXP1_A2") (pintype "bidirectional"))
    )
    (net (code "69") (name "unconnected-(J1-SSTXP2-PadB2)") (class "Default")
      (node (ref "J1") (pin "B2") (pinfunction "SSTXP2_B2") (pintype "bidirectional"))
    )
    (net (code "70") (name "unconnected-(U1-PB8-Pad61)") (class "Default")
      (node (ref "U1") (pin "61") (pinfunction "PB8_61") (pintype "bidirectional"))
    )
    (net (code "71") (name "unconnected-(U1-PB14-Pad35)") (class "Default")
      (node (ref "U1") (pin "35") (pinfunction "PB14_35") (pintype "bidirectional"))
    )
    (net (code "72") (name "unconnected-(U1-PC2-Pad10)") (class "Default")
      (node (ref "U1") (pin "10") (pinfunction "PC2_10") (pintype "bidirectional"))
    )
    (net (code "73") (name "unconnected-(U1-PC3-Pad11)") (class "Default")
      (node (ref "U1") (pin "11") (pinfunction "PC3_11") (pintype "bidirectional"))
    )
    (net (code "74") (name "unconnected-(U1-PC9-Pad40)") (class "Default")
      (node (ref "U1") (pin "40") (pinfunction "PC9_40") (pintype "bidirectional"))
    )
    (net (code "75") (name "unconnected-(U1-PC13-Pad2)") (class "Default")
      (node (ref "U1") (pin "2") (pinfunction "PC13_2") (pintype "bidirectional"))
    )
    (net (code "76") (name "unconnected-(U1-PD2-Pad54)") (class "Default")
      (node (ref "U1") (pin "54") (pinfunction "PD2_54") (pintype "bidirectional"))
    )
    (net (code "77") (name "unconnected-(U1-PF0-OSC_IN-Pad5)") (class "Default")
      (node (ref "U1") (pin "5") (pinfunction "PF0-OSC_IN_5") (pintype "bidirectional"))
    )
    (net (code "78") (name "unconnected-(U1-PF1-OSC_OUT-Pad6)") (class "Default")
      (node (ref "U1") (pin "6") (pinfunction "PF1-OSC_OUT_6") (pintype "bidirectional"))
    )
    (net (code "79") (name "unconnected-(U3-ALERT-Pad3)") (class "Default")
      (node (ref "U3") (pin "3") (pinfunction "ALERT_3") (pintype "open_collector"))
    )
    (net (code "80") (name "unconnected-(U3-TP-Pad9)") (class "Default")
      (node (ref "U3") (pin "9") (pinfunction "TP_9") (pintype "power_in"))
    )
  )
)
